# analog_sensor_input.net
KiCad netlist of a schematic drawn in Altium Designer
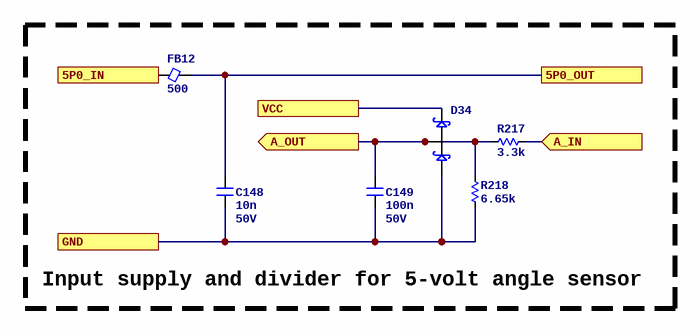
[diagram p0: analog_sensor_input.SchDoc]

(export (version "E")
  (design (tool "Eeschema 10.0.6"))
  (components
    (comp (ref "C148")
      (value "CL05B103KB5NNNC")
      (footprint "C0402")
      (fields
        (field (name "CAPACITANCE") "10n")
        (field (name "MANUFACTURER") "Samsung Electro-Mechanics")
        (field (name "VOLTAGE RATING") "50V")
      )
      (libsource (lib "database") (part "__template_cap"))
    )
    (comp (ref "C149")
      (value "CL05B104KB54PNC")
      (footprint "C0402")
      (fields
        (field (name "CAPACITANCE") "100n")
        (field (name "MANUFACTURER") "Samsung Electro-Mechanics")
        (field (name "VOLTAGE RATING") "50V")
      )
      (libsource (lib "database") (part "__template_cap"))
    )
    (comp (ref "D34")
      (value "BAT54SLT1G")
      (footprint "3SOT23")
      (description "DIODE SCHOTTKY DUAL 30V SOT23")
      (fields (field (name "MANUFACTURER") "ON Semiconductor"))
      (libsource (lib "SSCP") (part "SCHOTTKY_30V_DUAL_BAT54SLT1G"))
    )
    (comp (ref "FB12")
      (value "BLM15AX601SN1D")
      (footprint "FB0402")
      (fields (field (name "MANUFACTURER") "Murata Electronics") (field (name "CURRENT RATING (MA)") "500"))
      (libsource (lib "database") (part "__template_fb"))
    )
    (comp (ref "R217")
      (value "3.3k")
      (footprint "R0402")
      (fields
        (field (name "TOLERANCE") "1%")
        (field (name "MANUFACTURER PART NUMBER") "0402WGF3301TCE")
        (field (name "MANUFACTURER") "UNI-ROYAL(Uniroyal Elec)")
      )
      (libsource (lib "database") (part "__template_resistor"))
    )
    (comp (ref "R218")
      (value "6.65k")
      (footprint "R0402")
      (fields
        (field (name "TOLERANCE") "1%")
        (field (name "MANUFACTURER PART NUMBER") "FRC0402F6651TS")
        (field (name "MANUFACTURER") "FOJAN")
      )
      (libsource (lib "database") (part "__template_resistor"))
    )
  )
  (nets
    (net (code "1") (name "/5P0_IN") (class "Default") (node (ref "FB12") (pin "1") (pintype "passive")))
    (net (code "2") (name "/5P0_OUT") (class "Default")
      (node (ref "C148") (pin "1") (pintype "passive"))
      (node (ref "FB12") (pin "2") (pintype "passive"))
    )
    (net (code "3") (name "/A_IN") (class "Default") (node (ref "R217") (pin "2") (pintype "passive")))
    (net (code "4") (name "/A_OUT") (class "Default")
      (node (ref "C149") (pin "1") (pintype "passive"))
      (node (ref "D34") (pin "3") (pintype "passive"))
      (node (ref "R217") (pin "1") (pintype "passive"))
      (node (ref "R218") (pin "2") (pintype "passive"))
    )
    (net (code "5") (name "/GND") (class "Default")
      (node (ref "C148") (pin "2") (pintype "passive"))
      (node (ref "C149") (pin "2") (pintype "passive"))
      (node (ref "D34") (pin "1") (pintype "passive"))
      (node (ref "R218") (pin "1") (pintype "passive"))
    )
    (net (code "6") (name "/VCC") (class "Default") (node (ref "D34") (pin "2") (pintype "passive")))
  )
)
